# SDA7123.net
KiCad netlist of a schematic drawn in Altium Designer
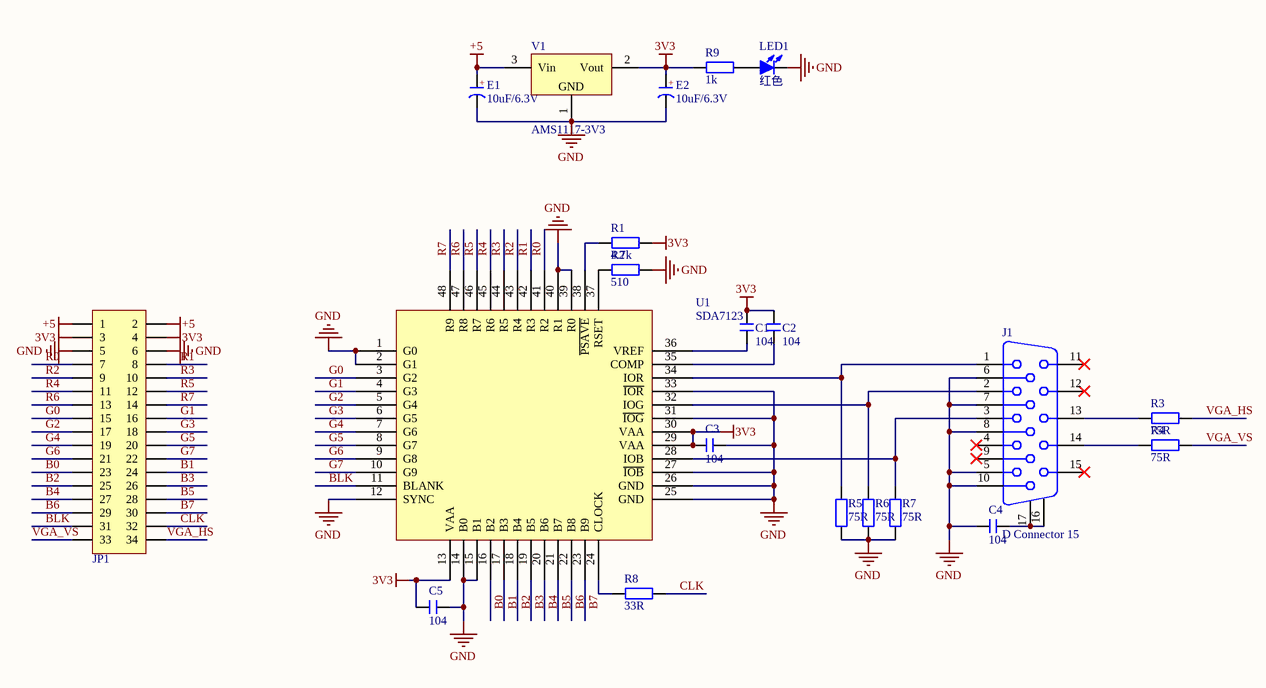
[diagram p0: SDA7123.SchDoc]

(export (version "E")
  (design (tool "Eeschema 10.0.6"))
  (components
    (comp (ref "C1")
      (value "104")
      (footprint "C 0805_L")
      (description "贴片电容")
      (libsource (lib "0.1 - 电阻-电容-电感") (part "C"))
    )
    (comp (ref "C2")
      (value "104")
      (footprint "C 0805_L")
      (description "贴片电容")
      (libsource (lib "0.1 - 电阻-电容-电感") (part "C"))
    )
    (comp (ref "C3")
      (value "104")
      (footprint "C 0805_L")
      (description "贴片电容")
      (libsource (lib "0.1 - 电阻-电容-电感") (part "C"))
    )
    (comp (ref "C4")
      (value "104")
      (footprint "C 0805_L")
      (description "贴片电容")
      (libsource (lib "0.1 - 电阻-电容-电感") (part "C"))
    )
    (comp (ref "C5")
      (value "104")
      (footprint "C 0805_L")
      (description "贴片电容")
      (libsource (lib "0.1 - 电阻-电容-电感") (part "C"))
    )
    (comp (ref "E1")
      (value "10uF/6.3V")
      (footprint "CD A(3216)")
      (description "贴片钽电容")
      (libsource (lib "0.1 - 电阻-电容-电感") (part "CT"))
    )
    (comp (ref "E2")
      (value "10uF/6.3V")
      (footprint "CD A(3216)")
      (description "贴片钽电容")
      (libsource (lib "0.1 - 电阻-电容-电感") (part "CT"))
    )
    (comp (ref "J1")
      (value "D Connector 15")
      (footprint "VGA15b")
      (description "VGA通讯端口")
      (fields (field (name "版权归属") "封装库来自淘宝 ID：黄晶宝石"))
      (libsource (lib "0.8 - 网口-音频插座") (part "D Connector 15"))
    )
    (comp (ref "JP1")
      (value "Header 2X11")
      (footprint "HDR2.54-LI-2x17P")
      (description "17*2P接插件")
      (fields (field (name "版权归属") "封装库来自淘宝 ID：黄晶宝石"))
      (libsource (lib "5.3 - 接插件-脚距2.54 (100mil) ") (part "Header 17X2"))
    )
    (comp (ref "LED1")
      (value "红色")
      (footprint "LED 0805B")
      (description "贴片LED")
      (fields (field (name "版权归属") "封装库来自淘宝 ID：黄晶宝石"))
      (libsource (lib "0.3 - LED发光二极管") (part "LED-SMD"))
    )
    (comp (ref "R1")
      (value "4.7k")
      (footprint "R 0805_L")
      (description "贴片电阻")
      (fields (field (name "版权归属") "来自淘宝 ID：黄晶宝石"))
      (libsource (lib "0.1 - 电阻-电容-电感") (part "R"))
    )
    (comp (ref "R2")
      (value "510")
      (footprint "R 0805_L")
      (description "贴片电阻")
      (fields (field (name "版权归属") "来自淘宝 ID：黄晶宝石"))
      (libsource (lib "0.1 - 电阻-电容-电感") (part "R"))
    )
    (comp (ref "R3")
      (value "75R")
      (footprint "R 0805_L")
      (description "贴片电阻")
      (fields (field (name "版权归属") "来自淘宝 ID：黄晶宝石"))
      (libsource (lib "0.1 - 电阻-电容-电感") (part "R"))
    )
    (comp (ref "R4")
      (value "75R")
      (footprint "R 0805_L")
      (description "贴片电阻")
      (fields (field (name "版权归属") "来自淘宝 ID：黄晶宝石"))
      (libsource (lib "0.1 - 电阻-电容-电感") (part "R"))
    )
    (comp (ref "R5")
      (value "75R")
      (footprint "R 0805_L")
      (description "贴片电阻")
      (fields (field (name "版权归属") "来自淘宝 ID：黄晶宝石"))
      (libsource (lib "0.1 - 电阻-电容-电感") (part "R"))
    )
    (comp (ref "R6")
      (value "75R")
      (footprint "R 0805_L")
      (description "贴片电阻")
      (fields (field (name "版权归属") "来自淘宝 ID：黄晶宝石"))
      (libsource (lib "0.1 - 电阻-电容-电感") (part "R"))
    )
    (comp (ref "R7")
      (value "75R")
      (footprint "R 0805_L")
      (description "贴片电阻")
      (fields (field (name "版权归属") "来自淘宝 ID：黄晶宝石"))
      (libsource (lib "0.1 - 电阻-电容-电感") (part "R"))
    )
    (comp (ref "R8")
      (value "33R")
      (footprint "R 0805_L")
      (description "贴片电阻")
      (fields (field (name "版权归属") "来自淘宝 ID：黄晶宝石"))
      (libsource (lib "0.1 - 电阻-电容-电感") (part "R"))
    )
    (comp (ref "R9")
      (value "1k")
      (footprint "R 0805_L")
      (description "贴片电阻")
      (fields (field (name "版权归属") "来自淘宝 ID：黄晶宝石"))
      (libsource (lib "0.1 - 电阻-电容-电感") (part "R"))
    )
    (comp (ref "U1")
      (value "SDA7123")
      (footprint "LQFP48 7X7_N")
      (libsource (lib "Schlib1") (part "SDA7123"))
    )
    (comp (ref "V1")
      (value "AMS1117-3V3")
      (footprint "SOT223_L")
      (description "三端稳压芯片")
      (libsource (lib "1.1 - 电源类芯片") (part "AMS1117"))
    )
  )
  (nets
    (net (code "1") (name "+5") (class "Default")
      (node (ref "E1") (pin "1") (pinfunction "A_1") (pintype "passive"))
      (node (ref "JP1") (pin "1") (pinfunction "1_1") (pintype "passive"))
      (node (ref "JP1") (pin "2") (pinfunction "2_2") (pintype "passive"))
      (node (ref "V1") (pin "3") (pinfunction "Vin_3") (pintype "passive"))
    )
    (net (code "2") (name "/B0") (class "Default")
      (node (ref "JP1") (pin "23") (pinfunction "23_23") (pintype "passive"))
      (node (ref "U1") (pin "16") (pinfunction "B2_16") (pintype "passive"))
    )
    (net (code "3") (name "/B1") (class "Default")
      (node (ref "JP1") (pin "24") (pinfunction "24_24") (pintype "passive"))
      (node (ref "U1") (pin "17") (pinfunction "B3_17") (pintype "passive"))
    )
    (net (code "4") (name "/B2") (class "Default")
      (node (ref "JP1") (pin "25") (pinfunction "25_25") (pintype "passive"))
      (node (ref "U1") (pin "18") (pinfunction "B4_18") (pintype "passive"))
    )
    (net (code "5") (name "/B3") (class "Default")
      (node (ref "JP1") (pin "26") (pinfunction "26_26") (pintype "passive"))
      (node (ref "U1") (pin "19") (pinfunction "B5_19") (pintype "passive"))
    )
    (net (code "6") (name "/B4") (class "Default")
      (node (ref "JP1") (pin "27") (pinfunction "27_27") (pintype "passive"))
      (node (ref "U1") (pin "20") (pinfunction "B6_20") (pintype "passive"))
    )
    (net (code "7") (name "/B5") (class "Default")
      (node (ref "JP1") (pin "28") (pinfunction "28_28") (pintype "passive"))
      (node (ref "U1") (pin "21") (pinfunction "B7_21") (pintype "passive"))
    )
    (net (code "8") (name "/B6") (class "Default")
      (node (ref "JP1") (pin "29") (pinfunction "29_29") (pintype "passive"))
      (node (ref "U1") (pin "22") (pinfunction "B8_22") (pintype "passive"))
    )
    (net (code "9") (name "/B7") (class "Default")
      (node (ref "JP1") (pin "30") (pinfunction "30_30") (pintype "passive"))
      (node (ref "U1") (pin "23") (pinfunction "B9_23") (pintype "passive"))
    )
    (net (code "10") (name "/BLK") (class "Default")
      (node (ref "JP1") (pin "31") (pinfunction "31_31") (pintype "passive"))
      (node (ref "U1") (pin "11") (pinfunction "BLANK_11") (pintype "passive"))
    )
    (net (code "11") (name "/CLK") (class "Default")
      (node (ref "JP1") (pin "32") (pinfunction "32_32") (pintype "passive"))
      (node (ref "R8") (pin "2") (pinfunction "2_2") (pintype "passive"))
    )
    (net (code "12") (name "/G0") (class "Default")
      (node (ref "JP1") (pin "15") (pinfunction "15_15") (pintype "passive"))
      (node (ref "U1") (pin "3") (pinfunction "G2_3") (pintype "passive"))
    )
    (net (code "13") (name "/G1") (class "Default")
      (node (ref "JP1") (pin "16") (pinfunction "16_16") (pintype "passive"))
      (node (ref "U1") (pin "4") (pinfunction "G3_4") (pintype "passive"))
    )
    (net (code "14") (name "/G2") (class "Default")
      (node (ref "JP1") (pin "17") (pinfunction "17_17") (pintype "passive"))
      (node (ref "U1") (pin "5") (pinfunction "G4_5") (pintype "passive"))
    )
    (net (code "15") (name "/G3") (class "Default")
      (node (ref "JP1") (pin "18") (pinfunction "18_18") (pintype "passive"))
      (node (ref "U1") (pin "6") (pinfunction "G5_6") (pintype "passive"))
    )
    (net (code "16") (name "/G4") (class "Default")
      (node (ref "JP1") (pin "19") (pinfunction "19_19") (pintype "passive"))
      (node (ref "U1") (pin "7") (pinfunction "G6_7") (pintype "passive"))
    )
    (net (code "17") (name "/G5") (class "Default")
      (node (ref "JP1") (pin "20") (pinfunction "20_20") (pintype "passive"))
      (node (ref "U1") (pin "8") (pinfunction "G7_8") (pintype "passive"))
    )
    (net (code "18") (name "/G6") (class "Default")
      (node (ref "JP1") (pin "21") (pinfunction "21_21") (pintype "passive"))
      (node (ref "U1") (pin "9") (pinfunction "G8_9") (pintype "passive"))
    )
    (net (code "19") (name "/G7") (class "Default")
      (node (ref "JP1") (pin "22") (pinfunction "22_22") (pintype "passive"))
      (node (ref "U1") (pin "10") (pinfunction "G9_10") (pintype "passive"))
    )
    (net (code "20") (name "/R0") (class "Default")
      (node (ref "JP1") (pin "7") (pinfunction "7_7") (pintype "passive"))
      (node (ref "U1") (pin "41") (pinfunction "R2_41") (pintype "passive"))
    )
    (net (code "21") (name "/R1") (class "Default")
      (node (ref "JP1") (pin "8") (pinfunction "8_8") (pintype "passive"))
      (node (ref "U1") (pin "42") (pinfunction "R3_42") (pintype "passive"))
    )
    (net (code "22") (name "/R2") (class "Default")
      (node (ref "JP1") (pin "9") (pinfunction "9_9") (pintype "passive"))
      (node (ref "U1") (pin "43") (pinfunction "R4_43") (pintype "passive"))
    )
    (net (code "23") (name "/R3") (class "Default")
      (node (ref "JP1") (pin "10") (pinfunction "10_10") (pintype "passive"))
      (node (ref "U1") (pin "44") (pinfunction "R5_44") (pintype "passive"))
    )
    (net (code "24") (name "/R4") (class "Default")
      (node (ref "JP1") (pin "11") (pinfunction "11_11") (pintype "passive"))
      (node (ref "U1") (pin "45") (pinfunction "R6_45") (pintype "passive"))
    )
    (net (code "25") (name "/R5") (class "Default")
      (node (ref "JP1") (pin "12") (pinfunction "12_12") (pintype "passive"))
      (node (ref "U1") (pin "46") (pinfunction "R7_46") (pintype "passive"))
    )
    (net (code "26") (name "/R6") (class "Default")
      (node (ref "JP1") (pin "13") (pinfunction "13_13") (pintype "passive"))
      (node (ref "U1") (pin "47") (pinfunction "R8_47") (pintype "passive"))
    )
    (net (code "27") (name "/R7") (class "Default")
      (node (ref "JP1") (pin "14") (pinfunction "14_14") (pintype "passive"))
      (node (ref "U1") (pin "48") (pinfunction "R9_48") (pintype "passive"))
    )
    (net (code "28") (name "/VGA_HS") (class "Default")
      (node (ref "JP1") (pin "34") (pinfunction "34_34") (pintype "passive"))
      (node (ref "R3") (pin "1") (pinfunction "1_1") (pintype "passive"))
    )
    (net (code "29") (name "/VGA_VS") (class "Default")
      (node (ref "JP1") (pin "33") (pinfunction "33_33") (pintype "passive"))
      (node (ref "R4") (pin "1") (pinfunction "1_1") (pintype "passive"))
    )
    (net (code "30") (name "3V3") (class "Default")
      (node (ref "C1") (pin "2") (pinfunction "2_2") (pintype "passive"))
      (node (ref "C2") (pin "2") (pinfunction "2_2") (pintype "passive"))
      (node (ref "C3") (pin "2") (pinfunction "2_2") (pintype "passive"))
      (node (ref "C5") (pin "1") (pinfunction "1_1") (pintype "passive"))
      (node (ref "E2") (pin "1") (pinfunction "A_1") (pintype "passive"))
      (node (ref "JP1") (pin "3") (pinfunction "3_3") (pintype "passive"))
      (node (ref "JP1") (pin "4") (pinfunction "4_4") (pintype "passive"))
      (node (ref "R1") (pin "2") (pinfunction "2_2") (pintype "passive"))
      (node (ref "R9") (pin "1") (pinfunction "1_1") (pintype "passive"))
      (node (ref "U1") (pin "13") (pinfunction "VAA_13") (pintype "passive"))
      (node (ref "U1") (pin "29") (pinfunction "VAA_29") (pintype "passive"))
      (node (ref "U1") (pin "30") (pinfunction "VAA_30") (pintype "passive"))
      (node (ref "V1") (pin "2") (pinfunction "Vout_2") (pintype "passive"))
    )
    (net (code "31") (name "GND") (class "Default")
      (node (ref "C3") (pin "1") (pinfunction "1_1") (pintype "passive"))
      (node (ref "C4") (pin "2") (pinfunction "2_2") (pintype "passive"))
      (node (ref "C5") (pin "2") (pinfunction "2_2") (pintype "passive"))
      (node (ref "E1") (pin "2") (pinfunction "K_2") (pintype "passive"))
      (node (ref "E2") (pin "2") (pinfunction "K_2") (pintype "passive"))
      (node (ref "J1") (pin "10") (pinfunction "10_10") (pintype "passive"))
      (node (ref "J1") (pin "5") (pinfunction "5_5") (pintype "passive"))
      (node (ref "J1") (pin "6") (pinfunction "6_6") (pintype "passive"))
      (node (ref "J1") (pin "7") (pinfunction "7_7") (pintype "passive"))
      (node (ref "J1") (pin "8") (pinfunction "8_8") (pintype "passive"))
      (node (ref "JP1") (pin "5") (pinfunction "5_5") (pintype "passive"))
      (node (ref "JP1") (pin "6") (pinfunction "6_6") (pintype "passive"))
      (node (ref "LED1") (pin "2") (pinfunction "K_2") (pintype "passive"))
      (node (ref "R2") (pin "2") (pinfunction "2_2") (pintype "passive"))
      (node (ref "R5") (pin "1") (pinfunction "1_1") (pintype "passive"))
      (node (ref "R6") (pin "1") (pinfunction "1_1") (pintype "passive"))
      (node (ref "R7") (pin "1") (pinfunction "1_1") (pintype "passive"))
      (node (ref "U1") (pin "1") (pinfunction "G0_1") (pintype "passive"))
      (node (ref "U1") (pin "12") (pinfunction "SYNC_12") (pintype "passive"))
      (node (ref "U1") (pin "14") (pinfunction "B0_14") (pintype "passive"))
      (node (ref "U1") (pin "15") (pinfunction "B1_15") (pintype "passive"))
      (node (ref "U1") (pin "2") (pinfunction "G1_2") (pintype "passive"))
      (node (ref "U1") (pin "25") (pinfunction "GND_25") (pintype "passive"))
      (node (ref "U1") (pin "26") (pinfunction "GND_26") (pintype "passive"))
      (node (ref "U1") (pin "27") (pinfunction "~{IOB}_27") (pintype "passive"))
      (node (ref "U1") (pin "31") (pinfunction "~{IOG}_31") (pintype "passive"))
      (node (ref "U1") (pin "33") (pinfunction "~{IOR}_33") (pintype "passive"))
      (node (ref "U1") (pin "39") (pinfunction "R0_39") (pintype "passive"))
      (node (ref "U1") (pin "40") (pinfunction "R1_40") (pintype "passive"))
      (node (ref "V1") (pin "1") (pinfunction "GND_1") (pintype "passive"))
    )
    (net (code "32") (name "Net-(J1-MH1)") (class "Default")
      (node (ref "C4") (pin "1") (pinfunction "1_1") (pintype "passive"))
      (node (ref "J1") (pin "16") (pinfunction "MH2_16") (pintype "passive"))
      (node (ref "J1") (pin "17") (pinfunction "MH1_17") (pintype "passive"))
    )
    (net (code "33") (name "Net-(J1-Pad13)") (class "Default")
      (node (ref "J1") (pin "13") (pinfunction "13_13") (pintype "passive"))
      (node (ref "R3") (pin "2") (pinfunction "2_2") (pintype "passive"))
    )
    (net (code "34") (name "Net-(J1-Pad14)") (class "Default")
      (node (ref "J1") (pin "14") (pinfunction "14_14") (pintype "passive"))
      (node (ref "R4") (pin "2") (pinfunction "2_2") (pintype "passive"))
    )
    (net (code "35") (name "Net-(LED1-A)") (class "Default")
      (node (ref "LED1") (pin "1") (pinfunction "A_1") (pintype "passive"))
      (node (ref "R9") (pin "2") (pinfunction "2_2") (pintype "passive"))
    )
    (net (code "36") (name "Net-(U1-CLOCK)") (class "Default")
      (node (ref "R8") (pin "1") (pinfunction "1_1") (pintype "passive"))
      (node (ref "U1") (pin "24") (pinfunction "CLOCK_24") (pintype "passive"))
    )
    (net (code "37") (name "Net-(U1-COMP)") (class "Default")
      (node (ref "C2") (pin "1") (pinfunction "1_1") (pintype "passive"))
      (node (ref "U1") (pin "35") (pinfunction "COMP_35") (pintype "passive"))
    )
    (net (code "38") (name "Net-(U1-IOB)") (class "Default")
      (node (ref "J1") (pin "3") (pinfunction "3_3") (pintype "passive"))
      (node (ref "R7") (pin "2") (pinfunction "2_2") (pintype "passive"))
      (node (ref "U1") (pin "28") (pinfunction "IOB_28") (pintype "passive"))
    )
    (net (code "39") (name "Net-(U1-IOG)") (class "Default")
      (node (ref "J1") (pin "2") (pinfunction "2_2") (pintype "passive"))
      (node (ref "R6") (pin "2") (pinfunction "2_2") (pintype "passive"))
      (node (ref "U1") (pin "32") (pinfunction "IOG_32") (pintype "passive"))
    )
    (net (code "40") (name "Net-(U1-IOR)") (class "Default")
      (node (ref "J1") (pin "1") (pinfunction "1_1") (pintype "passive"))
      (node (ref "R5") (pin "2") (pinfunction "2_2") (pintype "passive"))
      (node (ref "U1") (pin "34") (pinfunction "IOR_34") (pintype "passive"))
    )
    (net (code "41") (name "Net-(U1-RSET)") (class "Default")
      (node (ref "R2") (pin "1") (pinfunction "1_1") (pintype "passive"))
      (node (ref "U1") (pin "37") (pinfunction "RSET_37") (pintype "passive"))
    )
    (net (code "42") (name "Net-(U1-VREF)") (class "Default")
      (node (ref "C1") (pin "1") (pinfunction "1_1") (pintype "passive"))
      (node (ref "U1") (pin "36") (pinfunction "VREF_36") (pintype "passive"))
    )
    (net (code "43") (name "Net-(U1-~{PSAVE})") (class "Default")
      (node (ref "R1") (pin "1") (pinfunction "1_1") (pintype "passive"))
      (node (ref "U1") (pin "38") (pinfunction "~{PSAVE}_38") (pintype "passive"))
    )
    (net (code "44") (name "unconnected-(J1-Pad4)") (class "Default")
      (node (ref "J1") (pin "4") (pinfunction "4_4") (pintype "passive+no_connect"))
    )
    (net (code "45") (name "unconnected-(J1-Pad9)") (class "Default")
      (node (ref "J1") (pin "9") (pinfunction "9_9") (pintype "passive+no_connect"))
    )
    (net (code "46") (name "unconnected-(J1-Pad11)") (class "Default")
      (node (ref "J1") (pin "11") (pinfunction "11_11") (pintype "passive+no_connect"))
    )
    (net (code "47") (name "unconnected-(J1-Pad12)") (class "Default")
      (node (ref "J1") (pin "12") (pinfunction "12_12") (pintype "passive+no_connect"))
    )
    (net (code "48") (name "unconnected-(J1-Pad15)") (class "Default")
      (node (ref "J1") (pin "15") (pinfunction "15_15") (pintype "passive+no_connect"))
    )
  )
)
